# ASBB_5VBuck.net
KiCad netlist of a schematic drawn in Altium Designer
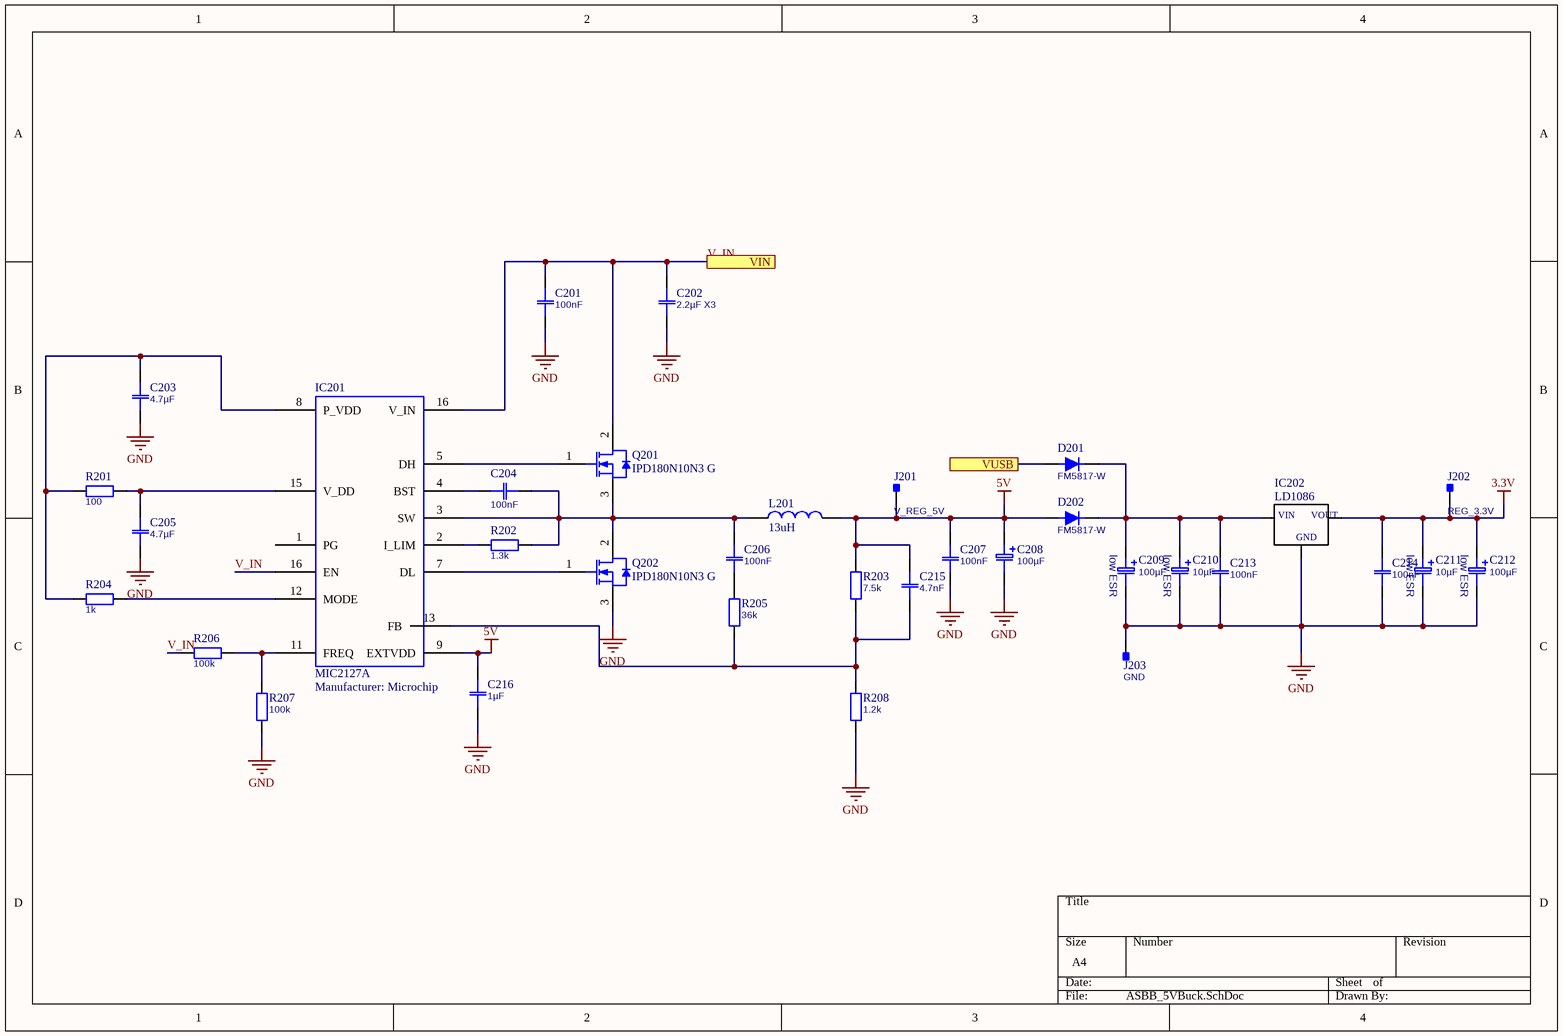
[diagram p0: ASBB_5VBuck.SchDoc]

(export (version "E")
  (design (tool "Eeschema 10.0.6"))
  (components
    (comp (ref "C201")
      (value "100nF")
      (footprint "CAP 1206/3216")
      (description "Capacitor")
      (fields (field (name "PARTNUMBER") "?"))
      (libsource (lib "FZI") (part "Capacitor"))
    )
    (comp (ref "C202")
      (value "2.2µF X3")
      (footprint "CAP 1206/3216")
      (description "Capacitor")
      (fields (field (name "PARTNUMBER") "?"))
      (libsource (lib "FZI") (part "Capacitor"))
    )
    (comp (ref "C203")
      (value "4.7µF")
      (footprint "CAP 1206/3216")
      (description "Capacitor")
      (fields (field (name "PARTNUMBER") "?"))
      (libsource (lib "FZI") (part "Capacitor"))
    )
    (comp (ref "C204")
      (value "100nF")
      (footprint "CAP 1206/3216")
      (description "Capacitor")
      (fields (field (name "PARTNUMBER") "?"))
      (libsource (lib "FZI") (part "Capacitor"))
    )
    (comp (ref "C205")
      (value "4.7µF")
      (footprint "CAP 1206/3216")
      (description "Capacitor")
      (fields (field (name "PARTNUMBER") "?"))
      (libsource (lib "FZI") (part "Capacitor"))
    )
    (comp (ref "C206")
      (value "100nF")
      (footprint "0603")
      (description "Capacitor")
      (fields (field (name "PARTNUMBER") "?"))
      (libsource (lib "FZI") (part "Capacitor"))
    )
    (comp (ref "C207")
      (value "100nF")
      (footprint "0603")
      (description "Capacitor")
      (fields (field (name "PARTNUMBER") "?"))
      (libsource (lib "FZI") (part "Capacitor"))
    )
    (comp (ref "C208")
      (value "100µF")
      (footprint "CAP ALUM 6.6MM")
      (description "Capacitor, polarised")
      (fields (field (name "PARTNUMBER") "?"))
      (libsource (lib "FZI") (part "Capacitor polarised"))
    )
    (comp (ref "C209")
      (value "100µF")
      (footprint "CAP ALUM 6.6MM")
      (description "Capacitor, polarised, low ESR")
      (fields (field (name "PARTNUMBER") "?"))
      (libsource (lib "FZI") (part "Capacitor polarised low ESR"))
    )
    (comp (ref "C210")
      (value "10µF")
      (footprint "CAP ALUM 6.6MM")
      (description "Capacitor, polarised, low ESR")
      (fields (field (name "PARTNUMBER") "?"))
      (libsource (lib "FZI") (part "Capacitor polarised low ESR"))
    )
    (comp (ref "C211")
      (value "10µF")
      (footprint "CAP ALUM 6.6MM")
      (description "Capacitor, polarised, low ESR")
      (fields (field (name "PARTNUMBER") "?"))
      (libsource (lib "FZI") (part "Capacitor polarised low ESR"))
    )
    (comp (ref "C212")
      (value "100µF")
      (footprint "CAP ALUM 6.6MM")
      (description "Capacitor, polarised, low ESR")
      (fields (field (name "PARTNUMBER") "?"))
      (libsource (lib "FZI") (part "Capacitor polarised low ESR"))
    )
    (comp (ref "C213")
      (value "100nF")
      (footprint "0603")
      (description "Capacitor")
      (fields (field (name "PARTNUMBER") "?"))
      (libsource (lib "FZI") (part "Capacitor"))
    )
    (comp (ref "C214")
      (value "100nF")
      (footprint "0603")
      (description "Capacitor")
      (fields (field (name "PARTNUMBER") "?"))
      (libsource (lib "FZI") (part "Capacitor"))
    )
    (comp (ref "C215")
      (value "4.7nF")
      (footprint "0603")
      (description "Capacitor")
      (fields (field (name "PARTNUMBER") "?"))
      (libsource (lib "FZI") (part "Capacitor"))
    )
    (comp (ref "C216")
      (value "1µF")
      (footprint "0603")
      (description "Capacitor")
      (fields (field (name "PARTNUMBER") "?"))
      (libsource (lib "FZI") (part "Capacitor"))
    )
    (comp (ref "D201")
      (value "FM5817-W")
      (footprint "SMB")
      (description "Diode")
      (fields (field (name "PARTNUMBER") "?"))
      (libsource (lib "FZI") (part "Diode"))
    )
    (comp (ref "D202")
      (value "FM5817-W")
      (footprint "SMB")
      (description "Diode")
      (fields (field (name "PARTNUMBER") "?"))
      (libsource (lib "FZI") (part "Diode"))
    )
    (comp (ref "IC201")
      (value "MIC2127A")
      (footprint "MCHP-QFN-MG16_N")
      (description "75V, Synchronous Buck Controller Featuring ADaptive On-Time Control")
      (fields (field (name "MANUFACTURER") "Microchip"))
      (libsource (lib "ASBB") (part "MIC2127A"))
    )
    (comp (ref "IC202")
      (value "LD1086")
      (footprint "D2PAK_LD1086(Primary)")
      (description "Semiconductors and Actives")
      (fields (field (name "MF") "STMicroelectronics"))
      (libsource (lib "LD1086") (part "LD1086"))
    )
    (comp (ref "J201")
      (value "V_REG_5V")
      (footprint "PIN1")
      (description "Pad, 1 Pin")
      (libsource (lib "") (part "Pad 1 Pin_1"))
    )
    (comp (ref "J202")
      (value "REG_3.3V")
      (footprint "PIN1")
      (description "Pad, 1 Pin")
      (libsource (lib "") (part "Pad 1 Pin_1"))
    )
    (comp (ref "J203")
      (value "GND")
      (footprint "PIN1")
      (description "Pad, 1 Pin")
      (libsource (lib "FZI") (part "Pad 1 Pin"))
    )
    (comp (ref "L201")
      (value "13uH")
      (footprint "WE-HCI_1365_WE-PERM")
      (description "WE-HCI SMD Flat Wire High Current Inductor, size 1365, 10A, 13uH")
      (fields (field (name "PART NUMBER") "7443551131") (field (name "PUBLISHER") "Wurth Elektronik"))
      (libsource (lib "ALTIUM-WE-HCI-rev17a") (part "7443551131"))
    )
    (comp (ref "Q201")
      (value "IPD180N10N3 G")
      (footprint "INF-PG-TO252-3-11_A_N")
      (fields (field (name "MANUFACTURER") "Infineon"))
      (libsource (lib "Infineon_Power_MOSFET") (part "IPD180N10N3 G"))
    )
    (comp (ref "Q202")
      (value "IPD180N10N3 G")
      (footprint "INF-PG-TO252-3-11_A_N")
      (fields (field (name "MANUFACTURER") "Infineon"))
      (libsource (lib "Infineon_Power_MOSFET") (part "IPD180N10N3 G"))
    )
    (comp (ref "R201")
      (value "100")
      (footprint "0603")
      (description "Resistor")
      (fields (field (name "PARTNUMBER") "?"))
      (libsource (lib "FZI") (part "Resistor"))
    )
    (comp (ref "R202")
      (value "1.3k")
      (footprint "0603")
      (description "Resistor")
      (fields (field (name "PARTNUMBER") "?"))
      (libsource (lib "FZI") (part "Resistor"))
    )
    (comp (ref "R203")
      (value "7.5k")
      (footprint "0603")
      (description "Resistor")
      (fields (field (name "PARTNUMBER") "?"))
      (libsource (lib "FZI") (part "Resistor"))
    )
    (comp (ref "R204")
      (value "1k")
      (footprint "0603")
      (description "Resistor")
      (fields (field (name "PARTNUMBER") "?"))
      (libsource (lib "FZI") (part "Resistor"))
    )
    (comp (ref "R205")
      (value "36k")
      (footprint "0603")
      (description "Resistor")
      (fields (field (name "PARTNUMBER") "?"))
      (libsource (lib "FZI") (part "Resistor"))
    )
    (comp (ref "R206")
      (value "100k")
      (footprint "CAP 1206/3216")
      (description "Resistor")
      (fields (field (name "PARTNUMBER") "?"))
      (libsource (lib "FZI") (part "Resistor"))
    )
    (comp (ref "R207")
      (value "100k")
      (footprint "CAP 1206/3216")
      (description "Resistor")
      (fields (field (name "PARTNUMBER") "?"))
      (libsource (lib "FZI") (part "Resistor"))
    )
    (comp (ref "R208")
      (value "1.2k")
      (footprint "0603")
      (description "Resistor")
      (fields (field (name "PARTNUMBER") "?"))
      (libsource (lib "FZI") (part "Resistor"))
    )
  )
  (nets
    (net (code "1") (name "/VUSB") (class "Default")
      (node (ref "D201") (pin "2") (pinfunction "A_2") (pintype "passive"))
    )
    (net (code "2") (name "/V_IN") (class "Default")
      (node (ref "C201") (pin "2") (pinfunction "2_2") (pintype "passive"))
      (node (ref "C202") (pin "2") (pinfunction "2_2") (pintype "passive"))
      (node (ref "IC201") (pin "16") (pinfunction "EN_16") (pintype "power_in"))
      (node (ref "Q201") (pin "2") (pinfunction "DRAIN_2") (pintype "passive"))
      (node (ref "R206") (pin "1") (pinfunction "1_1") (pintype "passive"))
    )
    (net (code "3") (name "3.3V") (class "Default")
      (node (ref "C211") (pin "1") (pinfunction "+_1") (pintype "passive"))
      (node (ref "C212") (pin "1") (pinfunction "+_1") (pintype "passive"))
      (node (ref "C214") (pin "2") (pinfunction "2_2") (pintype "passive"))
      (node (ref "IC202") (pin "VOUT") (pinfunction "VOUT_VOUT") (pintype "bidirectional"))
      (node (ref "J202") (pin "1") (pinfunction "1_1") (pintype "passive"))
    )
    (net (code "4") (name "5V") (class "Default")
      (node (ref "C207") (pin "1") (pinfunction "1_1") (pintype "passive"))
      (node (ref "C208") (pin "1") (pinfunction "+_1") (pintype "passive"))
      (node (ref "C215") (pin "1") (pinfunction "1_1") (pintype "passive"))
      (node (ref "C216") (pin "1") (pinfunction "1_1") (pintype "passive"))
      (node (ref "D202") (pin "2") (pinfunction "A_2") (pintype "passive"))
      (node (ref "IC201") (pin "9") (pinfunction "EXTVDD_9") (pintype "power_in"))
      (node (ref "J201") (pin "1") (pinfunction "1_1") (pintype "passive"))
      (node (ref "L201") (pin "2") (pinfunction "2_2") (pintype "passive"))
      (node (ref "R203") (pin "2") (pinfunction "2_2") (pintype "passive"))
    )
    (net (code "5") (name "GND") (class "Default")
      (node (ref "C201") (pin "1") (pinfunction "1_1") (pintype "passive"))
      (node (ref "C202") (pin "1") (pinfunction "1_1") (pintype "passive"))
      (node (ref "C203") (pin "2") (pinfunction "2_2") (pintype "passive"))
      (node (ref "C205") (pin "2") (pinfunction "2_2") (pintype "passive"))
      (node (ref "C207") (pin "2") (pinfunction "2_2") (pintype "passive"))
      (node (ref "C208") (pin "2") (pinfunction "-_2") (pintype "passive"))
      (node (ref "C209") (pin "2") (pinfunction "-_2") (pintype "passive"))
      (node (ref "C210") (pin "2") (pinfunction "-_2") (pintype "passive"))
      (node (ref "C211") (pin "2") (pinfunction "-_2") (pintype "passive"))
      (node (ref "C212") (pin "2") (pinfunction "-_2") (pintype "passive"))
      (node (ref "C213") (pin "1") (pinfunction "1_1") (pintype "passive"))
      (node (ref "C214") (pin "1") (pinfunction "1_1") (pintype "passive"))
      (node (ref "C216") (pin "2") (pinfunction "2_2") (pintype "passive"))
      (node (ref "IC202") (pin "GND") (pinfunction "GND_GND") (pintype "bidirectional"))
      (node (ref "J203") (pin "1") (pinfunction "1_1") (pintype "passive"))
      (node (ref "Q202") (pin "3") (pinfunction "SOURCE_3") (pintype "passive"))
      (node (ref "R207") (pin "1") (pinfunction "1_1") (pintype "passive"))
      (node (ref "R208") (pin "1") (pinfunction "1_1") (pintype "passive"))
    )
    (net (code "6") (name "Net-(C206-Pad2)") (class "Default")
      (node (ref "C206") (pin "2") (pinfunction "2_2") (pintype "passive"))
      (node (ref "R205") (pin "2") (pinfunction "2_2") (pintype "passive"))
    )
    (net (code "7") (name "Net-(C209-+)") (class "Default")
      (node (ref "C209") (pin "1") (pinfunction "+_1") (pintype "passive"))
      (node (ref "C210") (pin "1") (pinfunction "+_1") (pintype "passive"))
      (node (ref "C213") (pin "2") (pinfunction "2_2") (pintype "passive"))
      (node (ref "D201") (pin "1") (pinfunction "C_1") (pintype "passive"))
      (node (ref "D202") (pin "1") (pinfunction "C_1") (pintype "passive"))
      (node (ref "IC202") (pin "VIN") (pinfunction "VIN_VIN") (pintype "bidirectional"))
    )
    (net (code "8") (name "Net-(IC201-BST)") (class "Default")
      (node (ref "C204") (pin "2") (pinfunction "2_2") (pintype "passive"))
      (node (ref "IC201") (pin "4") (pinfunction "BST_4") (pintype "power_in"))
    )
    (net (code "9") (name "Net-(IC201-DH)") (class "Default")
      (node (ref "IC201") (pin "5") (pinfunction "DH_5") (pintype "power_in"))
      (node (ref "Q201") (pin "1") (pinfunction "GATE_1") (pintype "passive"))
    )
    (net (code "10") (name "Net-(IC201-DL)") (class "Default")
      (node (ref "IC201") (pin "7") (pinfunction "DL_7") (pintype "power_in"))
      (node (ref "Q202") (pin "1") (pinfunction "GATE_1") (pintype "passive"))
    )
    (net (code "11") (name "Net-(IC201-FB)") (class "Default")
      (node (ref "C215") (pin "2") (pinfunction "2_2") (pintype "passive"))
      (node (ref "IC201") (pin "13") (pinfunction "FB_13") (pintype "power_in"))
      (node (ref "R203") (pin "1") (pinfunction "1_1") (pintype "passive"))
      (node (ref "R205") (pin "1") (pinfunction "1_1") (pintype "passive"))
      (node (ref "R208") (pin "2") (pinfunction "2_2") (pintype "passive"))
    )
    (net (code "12") (name "Net-(IC201-FREQ)") (class "Default")
      (node (ref "IC201") (pin "11") (pinfunction "FREQ_11") (pintype "power_in"))
      (node (ref "R206") (pin "2") (pinfunction "2_2") (pintype "passive"))
      (node (ref "R207") (pin "2") (pinfunction "2_2") (pintype "passive"))
    )
    (net (code "13") (name "Net-(IC201-I_LIM)") (class "Default")
      (node (ref "IC201") (pin "2") (pinfunction "I_LIM_2") (pintype "power_in"))
      (node (ref "R202") (pin "1") (pinfunction "1_1") (pintype "passive"))
    )
    (net (code "14") (name "Net-(IC201-MODE)") (class "Default")
      (node (ref "IC201") (pin "12") (pinfunction "MODE_12") (pintype "power_in"))
      (node (ref "R204") (pin "2") (pinfunction "2_2") (pintype "passive"))
    )
    (net (code "15") (name "Net-(IC201-P_VDD)") (class "Default")
      (node (ref "C203") (pin "1") (pinfunction "1_1") (pintype "passive"))
      (node (ref "IC201") (pin "8") (pinfunction "P_VDD_8") (pintype "passive"))
      (node (ref "R201") (pin "1") (pinfunction "1_1") (pintype "passive"))
      (node (ref "R204") (pin "1") (pinfunction "1_1") (pintype "passive"))
    )
    (net (code "16") (name "Net-(IC201-SW)") (class "Default")
      (node (ref "C204") (pin "1") (pinfunction "1_1") (pintype "passive"))
      (node (ref "C206") (pin "1") (pinfunction "1_1") (pintype "passive"))
      (node (ref "IC201") (pin "3") (pinfunction "SW_3") (pintype "power_in"))
      (node (ref "L201") (pin "1") (pinfunction "1_1") (pintype "passive"))
      (node (ref "Q201") (pin "3") (pinfunction "SOURCE_3") (pintype "passive"))
      (node (ref "Q202") (pin "2") (pinfunction "DRAIN_2") (pintype "passive"))
      (node (ref "R202") (pin "2") (pinfunction "2_2") (pintype "passive"))
    )
    (net (code "17") (name "Net-(IC201-V_DD)") (class "Default")
      (node (ref "C205") (pin "1") (pinfunction "1_1") (pintype "passive"))
      (node (ref "IC201") (pin "15") (pinfunction "V_DD_15") (pintype "power_in"))
      (node (ref "R201") (pin "2") (pinfunction "2_2") (pintype "passive"))
    )
    (net (code "18") (name "unconnected-(IC201-PG-Pad1)") (class "Default")
      (node (ref "IC201") (pin "1") (pinfunction "PG_1") (pintype "passive"))
    )
  )
)
